# R2p_DCM_v2.net
KiCad netlist of a schematic drawn in EAGLE
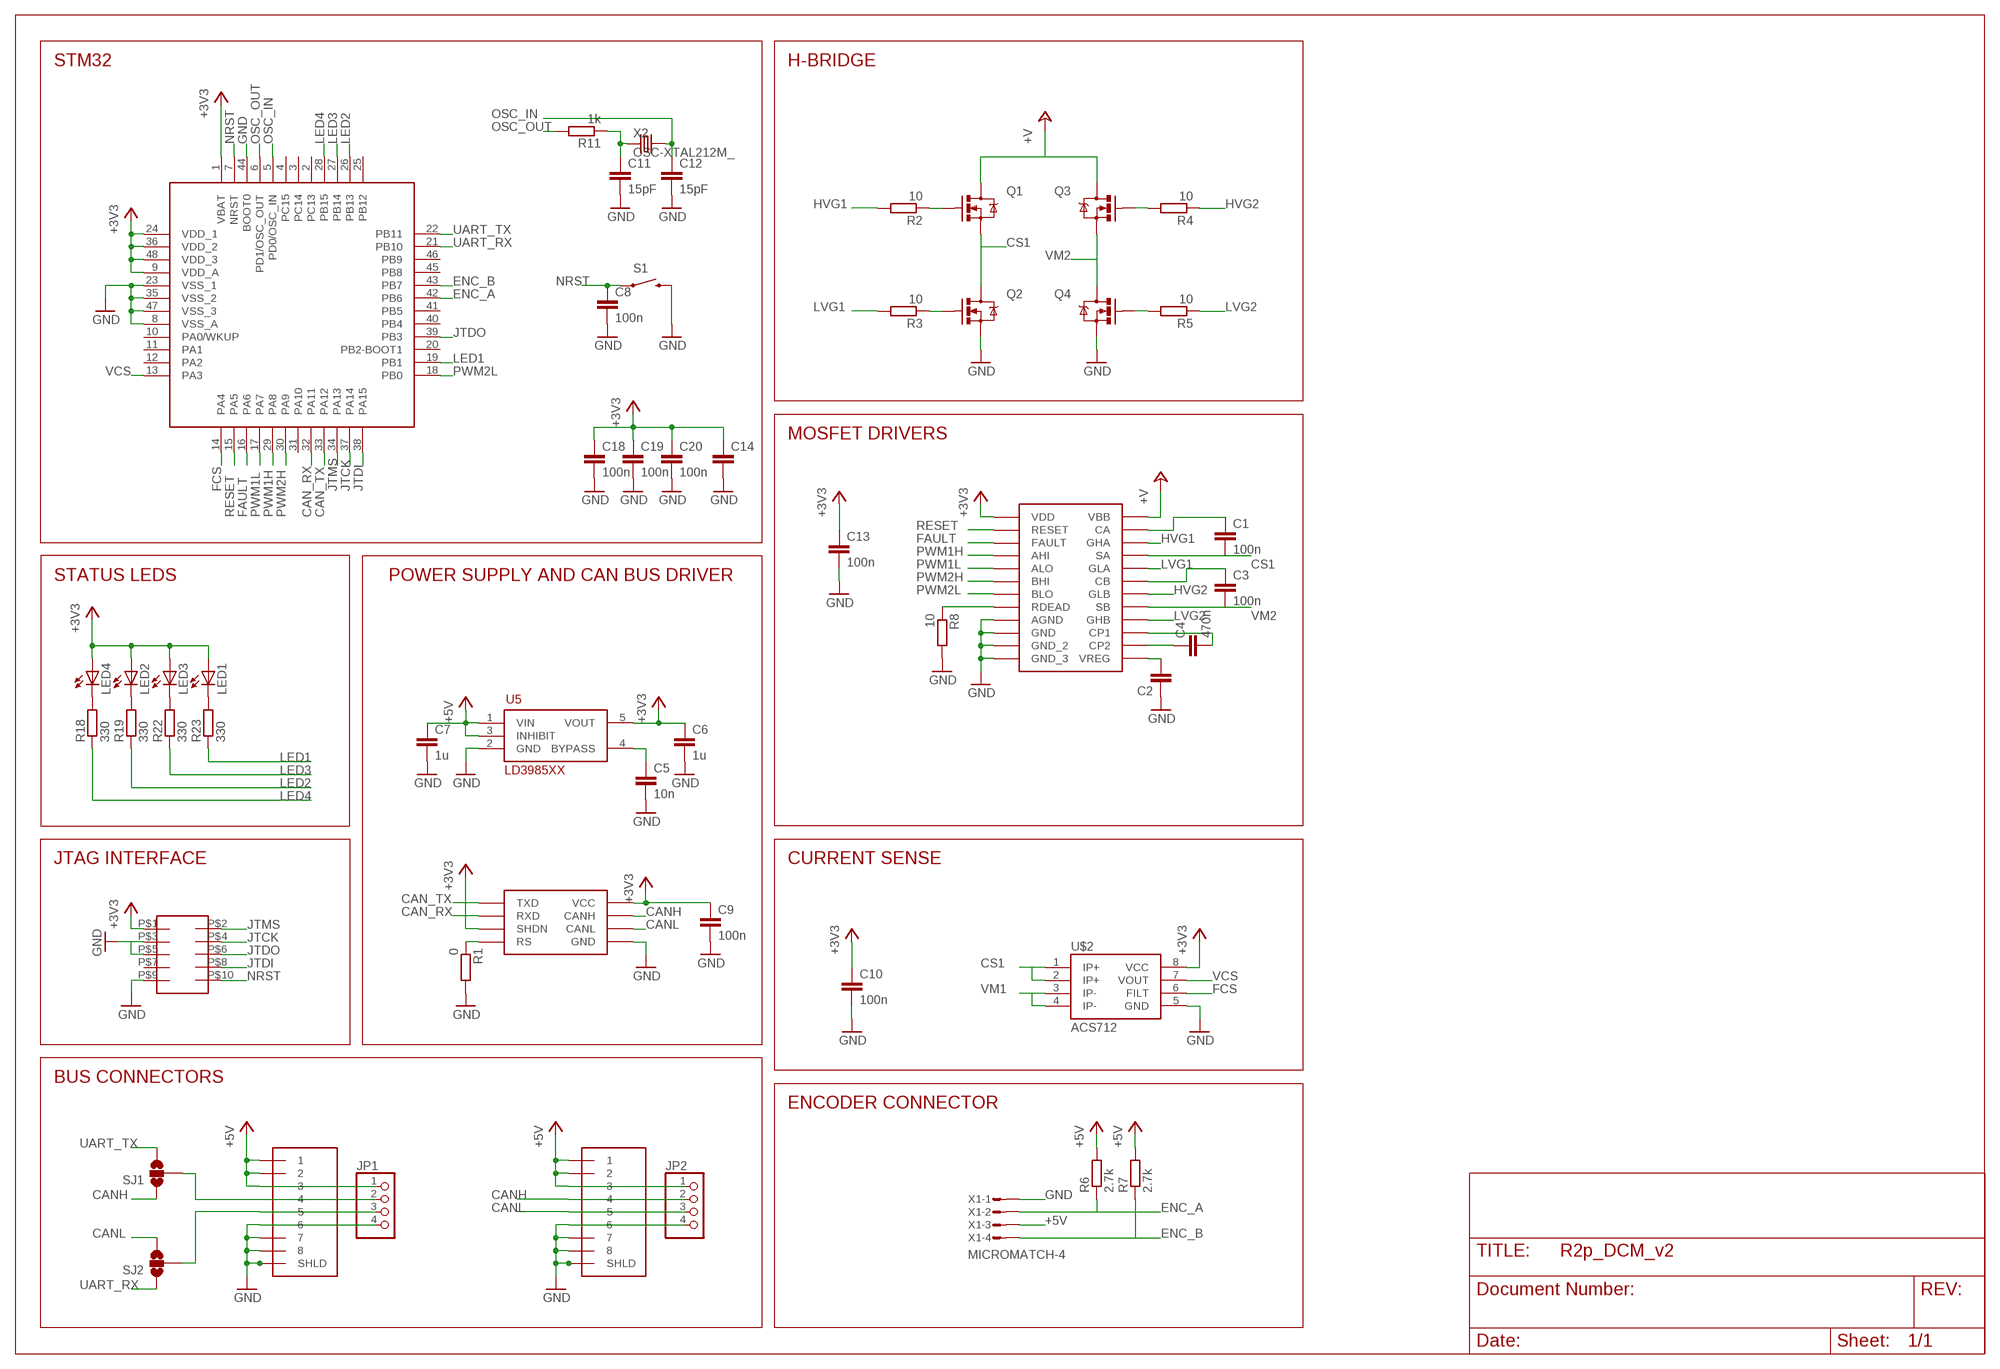
[diagram p0: schematic, sheet 1]

(export (version "E")
  (design (tool "Eeschema 10.0.6"))
  (components
    (comp (ref "1")
      (value "RJ45-43860")
      (footprint "eagle-import:0438600010")
      (libsource (lib "eagle-import") (part "RJ45-43860"))
    )
    (comp (ref "2")
      (value "RJ45-43860")
      (footprint "eagle-import:0438600010")
      (libsource (lib "eagle-import") (part "RJ45-43860"))
    )
    (comp (ref "C1")
      (value "100n")
      (footprint "eagle-import:C0603")
      (libsource (lib "eagle-import") (part "C-EUC0603"))
    )
    (comp (ref "C2")
      (value "C-EUC0805")
      (footprint "eagle-import:C0805")
      (libsource (lib "eagle-import") (part "C-EUC0805"))
    )
    (comp (ref "C3")
      (value "100n")
      (footprint "eagle-import:C0603")
      (libsource (lib "eagle-import") (part "C-EUC0603"))
    )
    (comp (ref "C4")
      (value "470n")
      (footprint "eagle-import:C0603")
      (libsource (lib "eagle-import") (part "C-EUC0603"))
    )
    (comp (ref "C5")
      (value "10n")
      (footprint "eagle-import:C0603")
      (libsource (lib "eagle-import") (part "C-EUC0603"))
    )
    (comp (ref "C6")
      (value "1u")
      (footprint "eagle-import:C0603")
      (libsource (lib "eagle-import") (part "C-EUC0603"))
    )
    (comp (ref "C7")
      (value "1u")
      (footprint "eagle-import:C0603")
      (libsource (lib "eagle-import") (part "C-EUC0603"))
    )
    (comp (ref "C8")
      (value "100n")
      (footprint "eagle-import:C0603")
      (libsource (lib "eagle-import") (part "C-EUC0603"))
    )
    (comp (ref "C9")
      (value "100n")
      (footprint "eagle-import:C0603")
      (libsource (lib "eagle-import") (part "C-EUC0603"))
    )
    (comp (ref "C10")
      (value "100n")
      (footprint "eagle-import:C0603")
      (libsource (lib "eagle-import") (part "C-EUC0603"))
    )
    (comp (ref "C11")
      (value "15pF")
      (footprint "eagle-import:C0603")
      (libsource (lib "eagle-import") (part "C-EUC0603"))
    )
    (comp (ref "C12")
      (value "15pF")
      (footprint "eagle-import:C0603")
      (libsource (lib "eagle-import") (part "C-EUC0603"))
    )
    (comp (ref "C13")
      (value "100n")
      (footprint "eagle-import:C0603")
      (libsource (lib "eagle-import") (part "C-EUC0603"))
    )
    (comp (ref "C14")
      (value "C-EUC0805")
      (footprint "eagle-import:C0805")
      (libsource (lib "eagle-import") (part "C-EUC0805"))
    )
    (comp (ref "C18")
      (value "100n")
      (footprint "eagle-import:C0603")
      (libsource (lib "eagle-import") (part "C-EUC0603"))
    )
    (comp (ref "C19")
      (value "100n")
      (footprint "eagle-import:C0603")
      (libsource (lib "eagle-import") (part "C-EUC0603"))
    )
    (comp (ref "C20")
      (value "100n")
      (footprint "eagle-import:C0603")
      (libsource (lib "eagle-import") (part "C-EUC0603"))
    )
    (comp (ref "JP1")
      (value "PINHD-1X4/90")
      (footprint "eagle-import:1X04_90")
      (libsource (lib "eagle-import") (part "PINHD-1X4/90"))
    )
    (comp (ref "JP2")
      (value "PINHD-1X4/90")
      (footprint "eagle-import:1X04_90")
      (libsource (lib "eagle-import") (part "PINHD-1X4/90"))
    )
    (comp (ref "LED1")
      (value "LEDCHIPLED_0805")
      (footprint "eagle-import:CHIPLED_0805")
      (libsource (lib "eagle-import") (part "LEDCHIPLED_0805"))
    )
    (comp (ref "LED2")
      (value "LEDCHIPLED_0805")
      (footprint "eagle-import:CHIPLED_0805")
      (libsource (lib "eagle-import") (part "LEDCHIPLED_0805"))
    )
    (comp (ref "LED3")
      (value "LEDCHIPLED_0805")
      (footprint "eagle-import:CHIPLED_0805")
      (libsource (lib "eagle-import") (part "LEDCHIPLED_0805"))
    )
    (comp (ref "LED4")
      (value "LEDCHIPLED_0805")
      (footprint "eagle-import:CHIPLED_0805")
      (libsource (lib "eagle-import") (part "LEDCHIPLED_0805"))
    )
    (comp (ref "Q1")
      (value "MOSFET-NCHANNELFDD8580")
      (footprint "eagle-import:DPAK")
      (libsource (lib "eagle-import") (part "MOSFET-NCHANNELFDD8580"))
    )
    (comp (ref "Q2")
      (value "MOSFET-NCHANNELFDD8580")
      (footprint "eagle-import:DPAK")
      (libsource (lib "eagle-import") (part "MOSFET-NCHANNELFDD8580"))
    )
    (comp (ref "Q3")
      (value "MOSFET-NCHANNELFDD8580")
      (footprint "eagle-import:DPAK")
      (libsource (lib "eagle-import") (part "MOSFET-NCHANNELFDD8580"))
    )
    (comp (ref "Q4")
      (value "MOSFET-NCHANNELFDD8580")
      (footprint "eagle-import:DPAK")
      (libsource (lib "eagle-import") (part "MOSFET-NCHANNELFDD8580"))
    )
    (comp (ref "R1")
      (value "0")
      (footprint "eagle-import:R0603")
      (libsource (lib "eagle-import") (part "R-EU_R0603"))
    )
    (comp (ref "R2")
      (value "10")
      (footprint "eagle-import:R0603")
      (libsource (lib "eagle-import") (part "R-EU_R0603"))
    )
    (comp (ref "R3")
      (value "10")
      (footprint "eagle-import:R0603")
      (libsource (lib "eagle-import") (part "R-EU_R0603"))
    )
    (comp (ref "R4")
      (value "10")
      (footprint "eagle-import:R0603")
      (libsource (lib "eagle-import") (part "R-EU_R0603"))
    )
    (comp (ref "R5")
      (value "10")
      (footprint "eagle-import:R0603")
      (libsource (lib "eagle-import") (part "R-EU_R0603"))
    )
    (comp (ref "R6")
      (value "2.7k")
      (footprint "eagle-import:R0603")
      (libsource (lib "eagle-import") (part "R-EU_R0603"))
    )
    (comp (ref "R7")
      (value "2.7k")
      (footprint "eagle-import:R0603")
      (libsource (lib "eagle-import") (part "R-EU_R0603"))
    )
    (comp (ref "R8")
      (value "10")
      (footprint "eagle-import:R0603")
      (libsource (lib "eagle-import") (part "R-EU_R0603"))
    )
    (comp (ref "R11")
      (value "1k")
      (footprint "eagle-import:R0603")
      (libsource (lib "eagle-import") (part "R-EU_R0603"))
    )
    (comp (ref "R18")
      (value "330")
      (footprint "eagle-import:R0603")
      (libsource (lib "eagle-import") (part "R-EU_R0603"))
    )
    (comp (ref "R19")
      (value "330")
      (footprint "eagle-import:R0603")
      (libsource (lib "eagle-import") (part "R-EU_R0603"))
    )
    (comp (ref "R22")
      (value "330")
      (footprint "eagle-import:R0603")
      (libsource (lib "eagle-import") (part "R-EU_R0603"))
    )
    (comp (ref "R23")
      (value "330")
      (footprint "eagle-import:R0603")
      (libsource (lib "eagle-import") (part "R-EU_R0603"))
    )
    (comp (ref "S1")
      (value "SWITCH-MOMENTARY-2-SMD-1101NE")
      (footprint "eagle-import:TACTILE-SWITCH-1101NE")
      (libsource (lib "eagle-import") (part "SWITCH-MOMENTARY-2-SMD-1101NE"))
    )
    (comp (ref "SJ1")
      (value "SOLDERJUMPER_2WAYPASTE1&2")
      (footprint "eagle-import:SJ_3_PASTE1&2")
      (libsource (lib "eagle-import") (part "SOLDERJUMPER_2WAYPASTE1&2"))
    )
    (comp (ref "SJ2")
      (value "SOLDERJUMPER_2WAYPASTE1&2")
      (footprint "eagle-import:SJ_3_PASTE1&2")
      (libsource (lib "eagle-import") (part "SOLDERJUMPER_2WAYPASTE1&2"))
    )
    (comp (ref "SOT1")
      (value "MAX3051")
      (footprint "eagle-import:SOT23-8L")
      (libsource (lib "eagle-import") (part "MAX3051"))
    )
    (comp (ref "U$1")
      (value "A4940")
      (footprint "eagle-import:TSSOP24")
      (libsource (lib "eagle-import") (part "A4940"))
    )
    (comp (ref "U$2")
      (value "ACS712")
      (footprint "eagle-import:SO08")
      (libsource (lib "eagle-import") (part "ACS712"))
    )
    (comp (ref "U$4")
      (value "FTSH-105")
      (footprint "eagle-import:FTSH-105")
      (libsource (lib "eagle-import") (part "FTSH-105"))
    )
    (comp (ref "U1")
      (value "STM32F103CX")
      (footprint "eagle-import:LQFP48")
      (libsource (lib "eagle-import") (part "STM32F103CX"))
    )
    (comp (ref "U5")
      (value "LD3985XX")
      (footprint "eagle-import:SOT23-5L")
      (libsource (lib "eagle-import") (part "LD3985XX"))
    )
    (comp (ref "X1")
      (value "MICROMATCH-4")
      (footprint "eagle-import:MICROMATCH-4")
      (libsource (lib "eagle-import") (part "MICROMATCH-4"))
    )
    (comp (ref "X2")
      (value "OSC-XTAL212M_")
      (footprint "eagle-import:4X6")
      (libsource (lib "eagle-import") (part "OSC-XTAL212M_"))
    )
  )
  (nets
    (net (code "1") (name "+3V3") (class "Default")
      (node (ref "C10") (pin "1") (pinfunction "1_1") (pintype "passive"))
      (node (ref "C13") (pin "1") (pinfunction "1_1") (pintype "passive"))
      (node (ref "C14") (pin "1") (pinfunction "1_1") (pintype "passive"))
      (node (ref "C18") (pin "1") (pinfunction "1_1") (pintype "passive"))
      (node (ref "C19") (pin "1") (pinfunction "1_1") (pintype "passive"))
      (node (ref "C20") (pin "1") (pinfunction "1_1") (pintype "passive"))
      (node (ref "C6") (pin "1") (pinfunction "1_1") (pintype "passive"))
      (node (ref "C9") (pin "1") (pinfunction "1_1") (pintype "passive"))
      (node (ref "LED1") (pin "A") (pinfunction "A_A") (pintype "passive"))
      (node (ref "LED2") (pin "A") (pinfunction "A_A") (pintype "passive"))
      (node (ref "LED3") (pin "A") (pinfunction "A_A") (pintype "passive"))
      (node (ref "LED4") (pin "A") (pinfunction "A_A") (pintype "passive"))
      (node (ref "SOT1") (pin "P$3") (pinfunction "VCC_P$3") (pintype "bidirectional"))
      (node (ref "SOT1") (pin "P$5") (pinfunction "SHDN_P$5") (pintype "bidirectional"))
      (node (ref "U$1") (pin "21") (pinfunction "VDD_21") (pintype "bidirectional"))
      (node (ref "U$2") (pin "8") (pinfunction "VCC_8") (pintype "bidirectional"))
      (node (ref "U$4") (pin "P$1") (pinfunction "P$1_P$1") (pintype "bidirectional"))
      (node (ref "U1") (pin "1") (pinfunction "VBAT_1") (pintype "bidirectional"))
      (node (ref "U1") (pin "24") (pinfunction "VDD_1_24") (pintype "bidirectional"))
      (node (ref "U1") (pin "36") (pinfunction "VDD_2_36") (pintype "bidirectional"))
      (node (ref "U1") (pin "48") (pinfunction "VDD_3_48") (pintype "bidirectional"))
      (node (ref "U1") (pin "9") (pinfunction "VDD_A_9") (pintype "bidirectional"))
      (node (ref "U5") (pin "5") (pinfunction "VOUT_5") (pintype "bidirectional"))
    )
    (net (code "2") (name "+5V") (class "Default")
      (node (ref "1") (pin "P$1") (pinfunction "1_P$1") (pintype "bidirectional"))
      (node (ref "1") (pin "P$2") (pinfunction "2_P$2") (pintype "bidirectional"))
      (node (ref "1") (pin "P$3") (pinfunction "3_P$3") (pintype "bidirectional"))
      (node (ref "2") (pin "P$1") (pinfunction "1_P$1") (pintype "bidirectional"))
      (node (ref "2") (pin "P$2") (pinfunction "2_P$2") (pintype "bidirectional"))
      (node (ref "2") (pin "P$3") (pinfunction "3_P$3") (pintype "bidirectional"))
      (node (ref "C7") (pin "1") (pinfunction "1_1") (pintype "passive"))
      (node (ref "JP1") (pin "1") (pinfunction "1_1") (pintype "passive"))
      (node (ref "JP2") (pin "1") (pinfunction "1_1") (pintype "passive"))
      (node (ref "R6") (pin "2") (pinfunction "2_2") (pintype "passive"))
      (node (ref "R7") (pin "2") (pinfunction "2_2") (pintype "passive"))
      (node (ref "U5") (pin "1") (pinfunction "VIN_1") (pintype "bidirectional"))
      (node (ref "U5") (pin "3") (pinfunction "INHIBIT_3") (pintype "bidirectional"))
      (node (ref "X1") (pin "3") (pinfunction "S_3") (pintype "passive"))
    )
    (net (code "3") (name "+V") (class "Default")
      (node (ref "Q1") (pin "4") (pinfunction "D_4") (pintype "passive"))
      (node (ref "Q3") (pin "4") (pinfunction "D_4") (pintype "passive"))
      (node (ref "U$1") (pin "12") (pinfunction "VBB_12") (pintype "bidirectional"))
    )
    (net (code "4") (name "/CANH") (class "Default")
      (node (ref "2") (pin "P$4") (pinfunction "4_P$4") (pintype "bidirectional"))
      (node (ref "JP2") (pin "2") (pinfunction "2_2") (pintype "passive"))
      (node (ref "SJ1") (pin "1") (pinfunction "1_1") (pintype "passive"))
      (node (ref "SOT1") (pin "P$7") (pinfunction "CANH_P$7") (pintype "bidirectional"))
    )
    (net (code "5") (name "/CANL") (class "Default")
      (node (ref "2") (pin "P$5") (pinfunction "5_P$5") (pintype "bidirectional"))
      (node (ref "JP2") (pin "3") (pinfunction "3_3") (pintype "passive"))
      (node (ref "SJ2") (pin "3") (pinfunction "3_3") (pintype "passive"))
      (node (ref "SOT1") (pin "P$6") (pinfunction "CANL_P$6") (pintype "bidirectional"))
    )
    (net (code "6") (name "/CAN_RX") (class "Default")
      (node (ref "SOT1") (pin "P$4") (pinfunction "RXD_P$4") (pintype "bidirectional"))
      (node (ref "U1") (pin "32") (pinfunction "PA11_32") (pintype "bidirectional"))
    )
    (net (code "7") (name "/CAN_TX") (class "Default")
      (node (ref "SOT1") (pin "P$1") (pinfunction "TXD_P$1") (pintype "bidirectional"))
      (node (ref "U1") (pin "33") (pinfunction "PA12_33") (pintype "bidirectional"))
    )
    (net (code "8") (name "/CS1") (class "Default")
      (node (ref "C1") (pin "2") (pinfunction "2_2") (pintype "passive"))
      (node (ref "Q1") (pin "3") (pinfunction "S_3") (pintype "passive"))
      (node (ref "Q2") (pin "4") (pinfunction "D_4") (pintype "passive"))
      (node (ref "U$1") (pin "10") (pinfunction "SA_10") (pintype "bidirectional"))
      (node (ref "U$2") (pin "1") (pinfunction "IP+_1") (pintype "bidirectional"))
      (node (ref "U$2") (pin "2") (pinfunction "IP+_2") (pintype "bidirectional"))
    )
    (net (code "9") (name "/ENC_A") (class "Default")
      (node (ref "R6") (pin "1") (pinfunction "1_1") (pintype "passive"))
      (node (ref "U1") (pin "42") (pinfunction "PB6_42") (pintype "bidirectional"))
      (node (ref "X1") (pin "2") (pinfunction "S_2") (pintype "passive"))
    )
    (net (code "10") (name "/ENC_B") (class "Default")
      (node (ref "R7") (pin "1") (pinfunction "1_1") (pintype "passive"))
      (node (ref "U1") (pin "43") (pinfunction "PB7_43") (pintype "bidirectional"))
      (node (ref "X1") (pin "4") (pinfunction "S_4") (pintype "passive"))
    )
    (net (code "11") (name "/FAULT") (class "Default")
      (node (ref "U$1") (pin "24") (pinfunction "FAULT_24") (pintype "bidirectional"))
      (node (ref "U1") (pin "16") (pinfunction "PA6_16") (pintype "bidirectional"))
    )
    (net (code "12") (name "/FCS") (class "Default")
      (node (ref "U$2") (pin "6") (pinfunction "FILT_6") (pintype "bidirectional"))
      (node (ref "U1") (pin "14") (pinfunction "PA4_14") (pintype "bidirectional"))
    )
    (net (code "13") (name "/HVG1") (class "Default")
      (node (ref "R2") (pin "2") (pinfunction "2_2") (pintype "passive"))
      (node (ref "U$1") (pin "9") (pinfunction "GHA_9") (pintype "bidirectional"))
    )
    (net (code "14") (name "/HVG2") (class "Default")
      (node (ref "R4") (pin "1") (pinfunction "1_1") (pintype "passive"))
      (node (ref "U$1") (pin "3") (pinfunction "GLB_3") (pintype "bidirectional"))
    )
    (net (code "15") (name "/JTCK") (class "Default")
      (node (ref "U$4") (pin "P$4") (pinfunction "P$4_P$4") (pintype "bidirectional"))
      (node (ref "U1") (pin "37") (pinfunction "PA14_37") (pintype "bidirectional"))
    )
    (net (code "16") (name "/JTDI") (class "Default")
      (node (ref "U$4") (pin "P$8") (pinfunction "P$8_P$8") (pintype "bidirectional"))
      (node (ref "U1") (pin "38") (pinfunction "PA15_38") (pintype "bidirectional"))
    )
    (net (code "17") (name "/JTDO") (class "Default")
      (node (ref "U$4") (pin "P$6") (pinfunction "P$6_P$6") (pintype "bidirectional"))
      (node (ref "U1") (pin "39") (pinfunction "PB3_39") (pintype "bidirectional"))
    )
    (net (code "18") (name "/JTMS") (class "Default")
      (node (ref "U$4") (pin "P$2") (pinfunction "P$2_P$2") (pintype "bidirectional"))
      (node (ref "U1") (pin "34") (pinfunction "PA13_34") (pintype "bidirectional"))
    )
    (net (code "19") (name "/LED1") (class "Default")
      (node (ref "R23") (pin "1") (pinfunction "1_1") (pintype "passive"))
      (node (ref "U1") (pin "19") (pinfunction "PB1_19") (pintype "bidirectional"))
    )
    (net (code "20") (name "/LED2") (class "Default")
      (node (ref "R19") (pin "1") (pinfunction "1_1") (pintype "passive"))
      (node (ref "U1") (pin "26") (pinfunction "PB13_26") (pintype "bidirectional"))
    )
    (net (code "21") (name "/LED3") (class "Default")
      (node (ref "R22") (pin "1") (pinfunction "1_1") (pintype "passive"))
      (node (ref "U1") (pin "27") (pinfunction "PB14_27") (pintype "bidirectional"))
    )
    (net (code "22") (name "/LED4") (class "Default")
      (node (ref "R18") (pin "1") (pinfunction "1_1") (pintype "passive"))
      (node (ref "U1") (pin "28") (pinfunction "PB15_28") (pintype "bidirectional"))
    )
    (net (code "23") (name "/LVG1") (class "Default")
      (node (ref "R3") (pin "2") (pinfunction "2_2") (pintype "passive"))
      (node (ref "U$1") (pin "11") (pinfunction "GLA_11") (pintype "bidirectional"))
    )
    (net (code "24") (name "/LVG2") (class "Default")
      (node (ref "R5") (pin "1") (pinfunction "1_1") (pintype "passive"))
      (node (ref "U$1") (pin "5") (pinfunction "GHB_5") (pintype "bidirectional"))
    )
    (net (code "25") (name "/NRST") (class "Default")
      (node (ref "C8") (pin "1") (pinfunction "1_1") (pintype "passive"))
      (node (ref "S1") (pin "P$1") (pinfunction "1_P$1") (pintype "passive"))
      (node (ref "U$4") (pin "P$10") (pinfunction "P$10_P$10") (pintype "bidirectional"))
      (node (ref "U1") (pin "7") (pinfunction "NRST_7") (pintype "bidirectional"))
    )
    (net (code "26") (name "/OSC_IN") (class "Default")
      (node (ref "C12") (pin "1") (pinfunction "1_1") (pintype "passive"))
      (node (ref "U1") (pin "5") (pinfunction "PD0/OSC_IN_5") (pintype "bidirectional"))
      (node (ref "X2") (pin "2") (pinfunction "X2_2") (pintype "bidirectional"))
    )
    (net (code "27") (name "/OSC_OUT") (class "Default")
      (node (ref "R11") (pin "2") (pinfunction "2_2") (pintype "passive"))
      (node (ref "U1") (pin "6") (pinfunction "PD1/OSC_OUT_6") (pintype "bidirectional"))
    )
    (net (code "28") (name "/PWM1H") (class "Default")
      (node (ref "U$1") (pin "20") (pinfunction "AHI_20") (pintype "bidirectional"))
      (node (ref "U1") (pin "29") (pinfunction "PA8_29") (pintype "bidirectional"))
    )
    (net (code "29") (name "/PWM1L") (class "Default")
      (node (ref "U$1") (pin "19") (pinfunction "ALO_19") (pintype "bidirectional"))
      (node (ref "U1") (pin "17") (pinfunction "PA7_17") (pintype "bidirectional"))
    )
    (net (code "30") (name "/PWM2H") (class "Default")
      (node (ref "U$1") (pin "18") (pinfunction "BHI_18") (pintype "bidirectional"))
      (node (ref "U1") (pin "30") (pinfunction "PA9_30") (pintype "bidirectional"))
    )
    (net (code "31") (name "/PWM2L") (class "Default")
      (node (ref "U$1") (pin "17") (pinfunction "BLO_17") (pintype "bidirectional"))
      (node (ref "U1") (pin "18") (pinfunction "PB0_18") (pintype "bidirectional"))
    )
    (net (code "32") (name "/RESET") (class "Default")
      (node (ref "U$1") (pin "1") (pinfunction "RESET_1") (pintype "bidirectional"))
      (node (ref "U1") (pin "15") (pinfunction "PA5_15") (pintype "bidirectional"))
    )
    (net (code "33") (name "/UART_RX") (class "Default")
      (node (ref "SJ2") (pin "1") (pinfunction "1_1") (pintype "passive"))
      (node (ref "U1") (pin "21") (pinfunction "PB10_21") (pintype "bidirectional"))
    )
    (net (code "34") (name "/UART_TX") (class "Default")
      (node (ref "SJ1") (pin "3") (pinfunction "3_3") (pintype "passive"))
      (node (ref "U1") (pin "22") (pinfunction "PB11_22") (pintype "bidirectional"))
    )
    (net (code "35") (name "/VCS") (class "Default")
      (node (ref "U$2") (pin "7") (pinfunction "VOUT_7") (pintype "bidirectional"))
      (node (ref "U1") (pin "13") (pinfunction "PA3_13") (pintype "bidirectional"))
    )
    (net (code "36") (name "/VM1") (class "Default")
      (node (ref "U$2") (pin "3") (pinfunction "IP-_3") (pintype "bidirectional"))
      (node (ref "U$2") (pin "4") (pinfunction "IP-_4") (pintype "bidirectional"))
    )
    (net (code "37") (name "/VM2") (class "Default")
      (node (ref "C3") (pin "2") (pinfunction "2_2") (pintype "passive"))
      (node (ref "Q3") (pin "3") (pinfunction "S_3") (pintype "passive"))
      (node (ref "Q4") (pin "4") (pinfunction "D_4") (pintype "passive"))
      (node (ref "U$1") (pin "4") (pinfunction "SB_4") (pintype "bidirectional"))
    )
    (net (code "38") (name "GND") (class "Default")
      (node (ref "1") (pin "P$10") (pinfunction "P$1_P$10") (pintype "power_in"))
      (node (ref "1") (pin "P$6") (pinfunction "6_P$6") (pintype "bidirectional"))
      (node (ref "1") (pin "P$7") (pinfunction "7_P$7") (pintype "bidirectional"))
      (node (ref "1") (pin "P$8") (pinfunction "8_P$8") (pintype "bidirectional"))
      (node (ref "1") (pin "P$9") (pinfunction "SHLD_P$9") (pintype "power_in"))
      (node (ref "2") (pin "P$10") (pinfunction "P$1_P$10") (pintype "power_in"))
      (node (ref "2") (pin "P$6") (pinfunction "6_P$6") (pintype "bidirectional"))
      (node (ref "2") (pin "P$7") (pinfunction "7_P$7") (pintype "bidirectional"))
      (node (ref "2") (pin "P$8") (pinfunction "8_P$8") (pintype "bidirectional"))
      (node (ref "2") (pin "P$9") (pinfunction "SHLD_P$9") (pintype "power_in"))
      (node (ref "C10") (pin "2") (pinfunction "2_2") (pintype "passive"))
      (node (ref "C11") (pin "2") (pinfunction "2_2") (pintype "passive"))
      (node (ref "C12") (pin "2") (pinfunction "2_2") (pintype "passive"))
      (node (ref "C13") (pin "2") (pinfunction "2_2") (pintype "passive"))
      (node (ref "C14") (pin "2") (pinfunction "2_2") (pintype "passive"))
      (node (ref "C18") (pin "2") (pinfunction "2_2") (pintype "passive"))
      (node (ref "C19") (pin "2") (pinfunction "2_2") (pintype "passive"))
      (node (ref "C2") (pin "1") (pinfunction "1_1") (pintype "passive"))
      (node (ref "C20") (pin "2") (pinfunction "2_2") (pintype "passive"))
      (node (ref "C5") (pin "2") (pinfunction "2_2") (pintype "passive"))
      (node (ref "C6") (pin "2") (pinfunction "2_2") (pintype "passive"))
      (node (ref "C7") (pin "2") (pinfunction "2_2") (pintype "passive"))
      (node (ref "C8") (pin "2") (pinfunction "2_2") (pintype "passive"))
      (node (ref "C9") (pin "2") (pinfunction "2_2") (pintype "passive"))
      (node (ref "JP1") (pin "4") (pinfunction "4_4") (pintype "passive"))
      (node (ref "JP2") (pin "4") (pinfunction "4_4") (pintype "passive"))
      (node (ref "Q2") (pin "3") (pinfunction "S_3") (pintype "passive"))
      (node (ref "Q4") (pin "3") (pinfunction "S_3") (pintype "passive"))
      (node (ref "R1") (pin "2") (pinfunction "2_2") (pintype "passive"))
      (node (ref "R8") (pin "2") (pinfunction "2_2") (pintype "passive"))
      (node (ref "S1") (pin "P$2") (pinfunction "2_P$2") (pintype "passive"))
      (node (ref "SOT1") (pin "P$2") (pinfunction "GND_P$2") (pintype "bidirectional"))
      (node (ref "U$1") (pin "15") (pinfunction "GND_2_15") (pintype "bidirectional"))
      (node (ref "U$1") (pin "16") (pinfunction "GND_3_16") (pintype "bidirectional"))
      (node (ref "U$1") (pin "2") (pinfunction "GND_2") (pintype "bidirectional"))
      (node (ref "U$1") (pin "22") (pinfunction "AGND_22") (pintype "bidirectional"))
      (node (ref "U$2") (pin "5") (pinfunction "GND_5") (pintype "bidirectional"))
      (node (ref "U$4") (pin "P$3") (pinfunction "P$3_P$3") (pintype "bidirectional"))
      (node (ref "U$4") (pin "P$9") (pinfunction "P$9_P$9") (pintype "bidirectional"))
      (node (ref "U1") (pin "23") (pinfunction "VSS_1_23") (pintype "bidirectional"))
      (node (ref "U1") (pin "35") (pinfunction "VSS_2_35") (pintype "bidirectional"))
      (node (ref "U1") (pin "44") (pinfunction "BOOT0_44") (pintype "bidirectional"))
      (node (ref "U1") (pin "47") (pinfunction "VSS_3_47") (pintype "bidirectional"))
      (node (ref "U1") (pin "8") (pinfunction "VSS_A_8") (pintype "bidirectional"))
      (node (ref "U5") (pin "2") (pinfunction "GND_2") (pintype "bidirectional"))
      (node (ref "X1") (pin "1") (pinfunction "S_1") (pintype "passive"))
    )
    (net (code "39") (name "Net-(1-4)") (class "Default")
      (node (ref "1") (pin "P$4") (pinfunction "4_P$4") (pintype "bidirectional"))
      (node (ref "JP1") (pin "2") (pinfunction "2_2") (pintype "passive"))
      (node (ref "SJ1") (pin "2") (pinfunction "2_2") (pintype "passive"))
    )
    (net (code "40") (name "Net-(1-5)") (class "Default")
      (node (ref "1") (pin "P$5") (pinfunction "5_P$5") (pintype "bidirectional"))
      (node (ref "JP1") (pin "3") (pinfunction "3_3") (pintype "passive"))
      (node (ref "SJ2") (pin "2") (pinfunction "2_2") (pintype "passive"))
    )
    (net (code "41") (name "Net-(LED1-PadC)") (class "Default")
      (node (ref "LED1") (pin "C") (pinfunction "C_C") (pintype "passive"))
      (node (ref "R23") (pin "2") (pinfunction "2_2") (pintype "passive"))
    )
    (net (code "42") (name "Net-(LED2-PadC)") (class "Default")
      (node (ref "LED2") (pin "C") (pinfunction "C_C") (pintype "passive"))
      (node (ref "R19") (pin "2") (pinfunction "2_2") (pintype "passive"))
    )
    (net (code "43") (name "Net-(LED3-PadC)") (class "Default")
      (node (ref "LED3") (pin "C") (pinfunction "C_C") (pintype "passive"))
      (node (ref "R22") (pin "2") (pinfunction "2_2") (pintype "passive"))
    )
    (net (code "44") (name "Net-(LED4-PadC)") (class "Default")
      (node (ref "LED4") (pin "C") (pinfunction "C_C") (pintype "passive"))
      (node (ref "R18") (pin "2") (pinfunction "2_2") (pintype "passive"))
    )
    (net (code "45") (name "Net-(Q1-G)") (class "Default")
      (node (ref "Q1") (pin "1") (pinfunction "G_1") (pintype "passive"))
      (node (ref "R2") (pin "1") (pinfunction "1_1") (pintype "passive"))
    )
    (net (code "46") (name "Net-(Q2-G)") (class "Default")
      (node (ref "Q2") (pin "1") (pinfunction "G_1") (pintype "passive"))
      (node (ref "R3") (pin "1") (pinfunction "1_1") (pintype "passive"))
    )
    (net (code "47") (name "Net-(Q3-G)") (class "Default")
      (node (ref "Q3") (pin "1") (pinfunction "G_1") (pintype "passive"))
      (node (ref "R4") (pin "2") (pinfunction "2_2") (pintype "passive"))
    )
    (net (code "48") (name "Net-(Q4-G)") (class "Default")
      (node (ref "Q4") (pin "1") (pinfunction "G_1") (pintype "passive"))
      (node (ref "R5") (pin "2") (pinfunction "2_2") (pintype "passive"))
    )
    (net (code "49") (name "Net-(SOT1-RS)") (class "Default")
      (node (ref "R1") (pin "1") (pinfunction "1_1") (pintype "passive"))
      (node (ref "SOT1") (pin "P$8") (pinfunction "RS_P$8") (pintype "bidirectional"))
    )
    (net (code "50") (name "Net-(U$1-CA)") (class "Default")
      (node (ref "C1") (pin "1") (pinfunction "1_1") (pintype "passive"))
      (node (ref "U$1") (pin "8") (pinfunction "CA_8") (pintype "bidirectional"))
    )
    (net (code "51") (name "Net-(U$1-CB)") (class "Default")
      (node (ref "C3") (pin "1") (pinfunction "1_1") (pintype "passive"))
      (node (ref "U$1") (pin "6") (pinfunction "CB_6") (pintype "bidirectional"))
    )
    (net (code "52") (name "Net-(U$1-CP1)") (class "Default")
      (node (ref "C4") (pin "2") (pinfunction "2_2") (pintype "passive"))
      (node (ref "U$1") (pin "14") (pinfunction "CP1_14") (pintype "bidirectional"))
    )
    (net (code "53") (name "Net-(U$1-CP2)") (class "Default")
      (node (ref "C4") (pin "1") (pinfunction "1_1") (pintype "passive"))
      (node (ref "U$1") (pin "13") (pinfunction "CP2_13") (pintype "bidirectional"))
    )
    (net (code "54") (name "Net-(U$1-RDEAD)") (class "Default")
      (node (ref "R8") (pin "1") (pinfunction "1_1") (pintype "passive"))
      (node (ref "U$1") (pin "23") (pinfunction "RDEAD_23") (pintype "bidirectional"))
    )
    (net (code "55") (name "Net-(U$1-VREG)") (class "Default")
      (node (ref "C2") (pin "2") (pinfunction "2_2") (pintype "passive"))
      (node (ref "U$1") (pin "7") (pinfunction "VREG_7") (pintype "bidirectional"))
    )
    (net (code "56") (name "Net-(U5-BYPASS)") (class "Default")
      (node (ref "C5") (pin "1") (pinfunction "1_1") (pintype "passive"))
      (node (ref "U5") (pin "4") (pinfunction "BYPASS_4") (pintype "bidirectional"))
    )
    (net (code "57") (name "Net-(X2-X1)") (class "Default")
      (node (ref "C11") (pin "1") (pinfunction "1_1") (pintype "passive"))
      (node (ref "R11") (pin "1") (pinfunction "1_1") (pintype "passive"))
      (node (ref "X2") (pin "1") (pinfunction "X1_1") (pintype "bidirectional"))
    )
    (net (code "58") (name "unconnected-(U$4-PadP$5)") (class "Default")
      (node (ref "U$4") (pin "P$5") (pinfunction "P$5_P$5") (pintype "bidirectional"))
    )
    (net (code "59") (name "unconnected-(U$4-PadP$7)") (class "Default")
      (node (ref "U$4") (pin "P$7") (pinfunction "P$7_P$7") (pintype "bidirectional"))
    )
    (net (code "60") (name "unconnected-(U1-PA0{slash}WKUP-Pad10)") (class "Default")
      (node (ref "U1") (pin "10") (pinfunction "PA0/WKUP_10") (pintype "bidirectional"))
    )
    (net (code "61") (name "unconnected-(U1-PA1-Pad11)") (class "Default")
      (node (ref "U1") (pin "11") (pinfunction "PA1_11") (pintype "bidirectional"))
    )
    (net (code "62") (name "unconnected-(U1-PA2-Pad12)") (class "Default")
      (node (ref "U1") (pin "12") (pinfunction "PA2_12") (pintype "bidirectional"))
    )
    (net (code "63") (name "unconnected-(U1-PA10-Pad31)") (class "Default")
      (node (ref "U1") (pin "31") (pinfunction "PA10_31") (pintype "bidirectional"))
    )
    (net (code "64") (name "unconnected-(U1-PB2-BOOT1-Pad20)") (class "Default")
      (node (ref "U1") (pin "20") (pinfunction "PB2-BOOT1_20") (pintype "bidirectional"))
    )
    (net (code "65") (name "unconnected-(U1-PB4-Pad40)") (class "Default")
      (node (ref "U1") (pin "40") (pinfunction "PB4_40") (pintype "bidirectional"))
    )
    (net (code "66") (name "unconnected-(U1-PB5-Pad41)") (class "Default")
      (node (ref "U1") (pin "41") (pinfunction "PB5_41") (pintype "bidirectional"))
    )
    (net (code "67") (name "unconnected-(U1-PB8-Pad45)") (class "Default")
      (node (ref "U1") (pin "45") (pinfunction "PB8_45") (pintype "bidirectional"))
    )
    (net (code "68") (name "unconnected-(U1-PB9-Pad46)") (class "Default")
      (node (ref "U1") (pin "46") (pinfunction "PB9_46") (pintype "bidirectional"))
    )
    (net (code "69") (name "unconnected-(U1-PB12-Pad25)") (class "Default")
      (node (ref "U1") (pin "25") (pinfunction "PB12_25") (pintype "bidirectional"))
    )
    (net (code "70") (name "unconnected-(U1-PC13-Pad2)") (class "Default")
      (node (ref "U1") (pin "2") (pinfunction "PC13_2") (pintype "bidirectional"))
    )
    (net (code "71") (name "unconnected-(U1-PC14-Pad3)") (class "Default")
      (node (ref "U1") (pin "3") (pinfunction "PC14_3") (pintype "bidirectional"))
    )
    (net (code "72") (name "unconnected-(U1-PC15-Pad4)") (class "Default")
      (node (ref "U1") (pin "4") (pinfunction "PC15_4") (pintype "bidirectional"))
    )
  )
)
